# BleepDrum.net
KiCad netlist of a schematic drawn in EAGLE
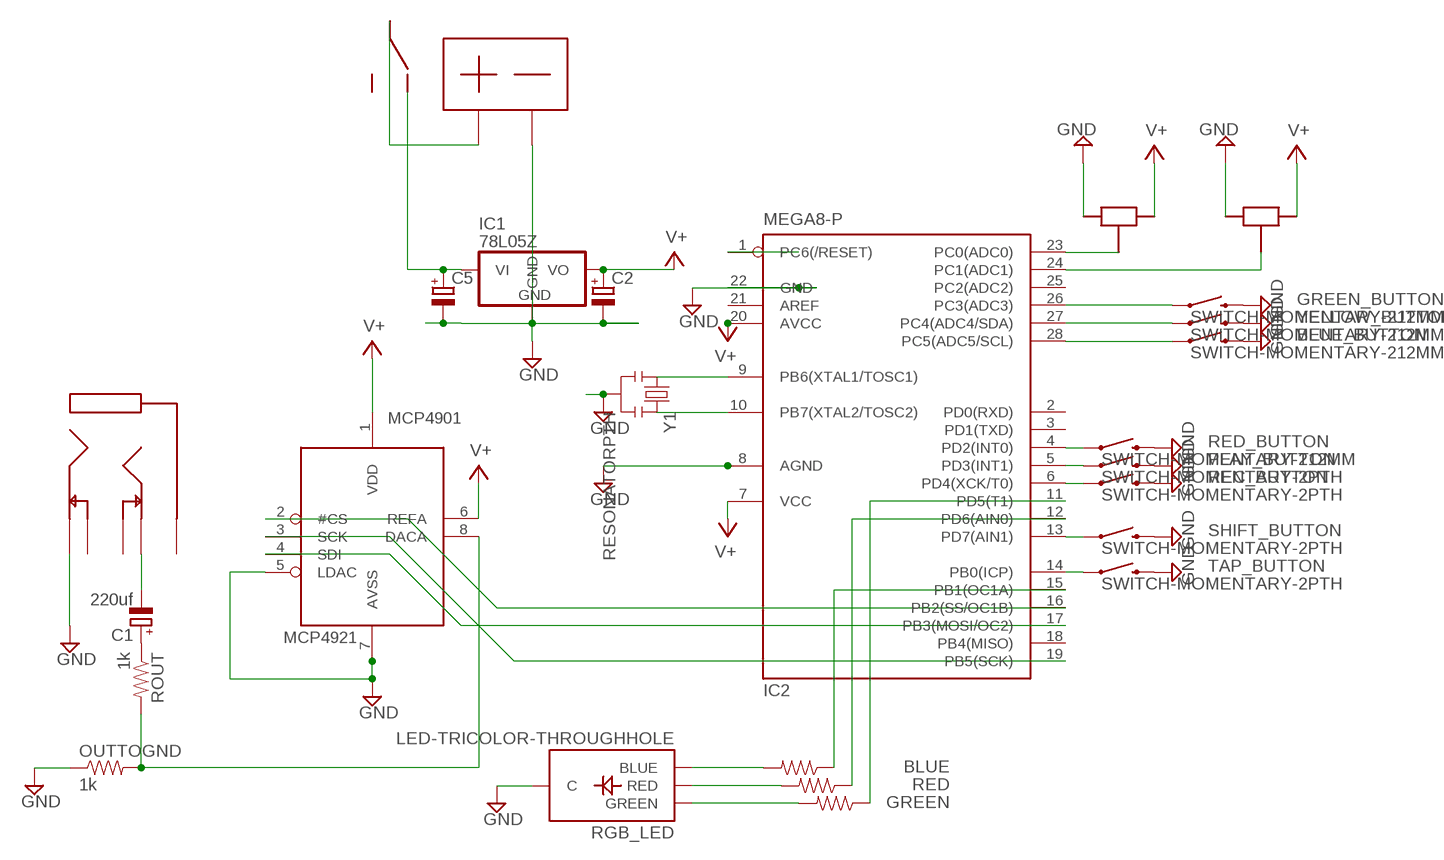
[diagram p0: schematic, sheet 1]

(export (version "E")
  (design (tool "Eeschema 10.0.6"))
  (components
    (comp (ref "BLUE")
      (value "RESISTORPTH-1/6W")
      (footprint "eagle-import:1_6W-RES")
      (libsource (lib "eagle-import") (part "RESISTORPTH-1/6W"))
    )
    (comp (ref "BLUE_BUTTON")
      (value "SWITCH-MOMENTARY-212MM")
      (footprint "eagle-import:TACTILE-PTH-12MM")
      (libsource (lib "eagle-import") (part "SWITCH-MOMENTARY-212MM"))
    )
    (comp (ref "C1")
      (value "220uf")
      (footprint "eagle-import:E2,5-6")
      (libsource (lib "eagle-import") (part "CPOL-EUE2.5-6"))
    )
    (comp (ref "C2")
      (value "CPOL-EUE2.5-6")
      (footprint "eagle-import:E2,5-6")
      (libsource (lib "eagle-import") (part "CPOL-EUE2.5-6"))
    )
    (comp (ref "C5")
      (value "CPOL-EUE2.5-6")
      (footprint "eagle-import:E2,5-6")
      (libsource (lib "eagle-import") (part "CPOL-EUE2.5-6"))
    )
    (comp (ref "GREEN")
      (value "RESISTORPTH-1/6W")
      (footprint "eagle-import:1_6W-RES")
      (libsource (lib "eagle-import") (part "RESISTORPTH-1/6W"))
    )
    (comp (ref "GREEN_BUTTON")
      (value "SWITCH-MOMENTARY-212MM")
      (footprint "eagle-import:TACTILE-PTH-12MM")
      (libsource (lib "eagle-import") (part "SWITCH-MOMENTARY-212MM"))
    )
    (comp (ref "IC1")
      (value "78L05Z")
      (footprint "eagle-import:TO92")
      (libsource (lib "eagle-import") (part "78ZL05"))
    )
    (comp (ref "IC2")
      (value "MEGA8-P")
      (footprint "eagle-import:DIL28-3")
      (libsource (lib "eagle-import") (part "MEGA8-P"))
    )
    (comp (ref "LEFT_POT")
      (value "POT")
      (footprint "eagle-import:POT")
      (libsource (lib "eagle-import") (part "POT"))
    )
    (comp (ref "MCP4901")
      (value "MCP4921")
      (footprint "eagle-import:DIL08")
      (libsource (lib "eagle-import") (part "MCP4921"))
    )
    (comp (ref "OUTTOGND")
      (value "1k")
      (footprint "eagle-import:1_6W-RES")
      (libsource (lib "eagle-import") (part "RESISTORPTH-1/6W"))
    )
    (comp (ref "PLAY_BUTTON")
      (value "SWITCH-MOMENTARY-2PTH")
      (footprint "eagle-import:TACTILE-PTH")
      (libsource (lib "eagle-import") (part "SWITCH-MOMENTARY-2PTH"))
    )
    (comp (ref "REC_BUTTON")
      (value "SWITCH-MOMENTARY-2PTH")
      (footprint "eagle-import:TACTILE-PTH")
      (libsource (lib "eagle-import") (part "SWITCH-MOMENTARY-2PTH"))
    )
    (comp (ref "RED")
      (value "RESISTORPTH-1/6W")
      (footprint "eagle-import:1_6W-RES")
      (libsource (lib "eagle-import") (part "RESISTORPTH-1/6W"))
    )
    (comp (ref "RED_BUTTON")
      (value "SWITCH-MOMENTARY-212MM")
      (footprint "eagle-import:TACTILE-PTH-12MM")
      (libsource (lib "eagle-import") (part "SWITCH-MOMENTARY-212MM"))
    )
    (comp (ref "RGB_LED")
      (value "LED-TRICOLOR-THROUGHHOLE")
      (footprint "eagle-import:LED-TRICOLOR-THROUGHHOLE")
      (libsource (lib "eagle-import") (part "LED-TRICOLOR-THROUGHHOLE"))
    )
    (comp (ref "RIGHT_POT")
      (value "POT")
      (footprint "eagle-import:POT")
      (libsource (lib "eagle-import") (part "POT"))
    )
    (comp (ref "ROUT")
      (value "1k")
      (footprint "eagle-import:1_6W-RES")
      (libsource (lib "eagle-import") (part "RESISTORPTH-1/6W"))
    )
    (comp (ref "SHIFT_BUTTON")
      (value "SWITCH-MOMENTARY-2PTH")
      (footprint "eagle-import:TACTILE-PTH")
      (libsource (lib "eagle-import") (part "SWITCH-MOMENTARY-2PTH"))
    )
    (comp (ref "SW1")
      (value "SLIDE_HORIZ_OS")
      (footprint "eagle-import:SLIDE_HORIZ_OS")
      (libsource (lib "eagle-import") (part "SLIDE_HORIZ_OS"))
    )
    (comp (ref "TAP_BUTTON")
      (value "SWITCH-MOMENTARY-2PTH")
      (footprint "eagle-import:TACTILE-PTH")
      (libsource (lib "eagle-import") (part "SWITCH-MOMENTARY-2PTH"))
    )
    (comp (ref "U$7")
      (value "9VSMALPINS")
      (footprint "eagle-import:9VSMALLPINS")
      (libsource (lib "eagle-import") (part "9VSMALPINS"))
    )
    (comp (ref "U$8")
      (value "1/8STEREO")
      (footprint "eagle-import:1_8STEREO")
      (libsource (lib "eagle-import") (part "1/8STEREO"))
    )
    (comp (ref "Y1")
      (value "RESONATORPTH")
      (footprint "eagle-import:RESONATOR-PTH")
      (libsource (lib "eagle-import") (part "RESONATORPTH"))
    )
    (comp (ref "YELLOW_BUTTON")
      (value "SWITCH-MOMENTARY-212MM")
      (footprint "eagle-import:TACTILE-PTH-12MM")
      (libsource (lib "eagle-import") (part "SWITCH-MOMENTARY-212MM"))
    )
  )
  (nets
    (net (code "1") (name "GND") (class "Default")
      (node (ref "BLUE_BUTTON") (pin "3") (pinfunction "2_3") (pintype "passive"))
      (node (ref "C2") (pin "-") (pinfunction "-_-") (pintype "passive"))
      (node (ref "C5") (pin "-") (pinfunction "-_-") (pintype "passive"))
      (node (ref "GREEN_BUTTON") (pin "3") (pinfunction "2_3") (pintype "passive"))
      (node (ref "IC1") (pin "2") (pinfunction "GND_2") (pintype "passive"))
      (node (ref "IC2") (pin "22") (pinfunction "GND_22") (pintype "power_in"))
      (node (ref "IC2") (pin "8") (pinfunction "AGND_8") (pintype "power_in"))
      (node (ref "LEFT_POT") (pin "P$3") (pinfunction "P$3_P$3") (pintype "bidirectional"))
      (node (ref "MCP4901") (pin "5") (pinfunction "LDAC_5") (pintype "input"))
      (node (ref "MCP4901") (pin "7") (pinfunction "AVSS_7") (pintype "power_in"))
      (node (ref "OUTTOGND") (pin "1") (pinfunction "1_1") (pintype "passive"))
      (node (ref "PLAY_BUTTON") (pin "3") (pinfunction "2_3") (pintype "passive"))
      (node (ref "REC_BUTTON") (pin "3") (pinfunction "2_3") (pintype "passive"))
      (node (ref "RED_BUTTON") (pin "3") (pinfunction "2_3") (pintype "passive"))
      (node (ref "RGB_LED") (pin "GND") (pinfunction "C_GND") (pintype "bidirectional"))
      (node (ref "RIGHT_POT") (pin "P$3") (pinfunction "P$3_P$3") (pintype "bidirectional"))
      (node (ref "SHIFT_BUTTON") (pin "3") (pinfunction "2_3") (pintype "passive"))
      (node (ref "TAP_BUTTON") (pin "3") (pinfunction "2_3") (pintype "passive"))
      (node (ref "U$7") (pin "P$2") (pinfunction "P$2_P$2") (pintype "bidirectional"))
      (node (ref "U$8") (pin "P$2") (pinfunction "P$2_P$2") (pintype "bidirectional"))
      (node (ref "Y1") (pin "2") (pinfunction "2_2") (pintype "passive"))
      (node (ref "YELLOW_BUTTON") (pin "3") (pinfunction "2_3") (pintype "passive"))
    )
    (net (code "2") (name "Net-(C1-Pad+)") (class "Default")
      (node (ref "C1") (pin "+") (pinfunction "+_+") (pintype "passive"))
      (node (ref "ROUT") (pin "1") (pinfunction "1_1") (pintype "passive"))
    )
    (net (code "3") (name "Net-(C1-Pad-)") (class "Default")
      (node (ref "C1") (pin "-") (pinfunction "-_-") (pintype "passive"))
      (node (ref "U$8") (pin "P$5") (pinfunction "P$5_P$5") (pintype "bidirectional"))
    )
    (net (code "4") (name "Net-(IC1-VI)") (class "Default")
      (node (ref "C5") (pin "+") (pinfunction "+_+") (pintype "passive"))
      (node (ref "IC1") (pin "3") (pinfunction "VI_3") (pintype "input"))
      (node (ref "SW1") (pin "P$2") (pinfunction "P$2_P$2") (pintype "bidirectional"))
    )
    (net (code "5") (name "Net-(IC2-PB0(ICP))") (class "Default")
      (node (ref "IC2") (pin "14") (pinfunction "PB0(ICP)_14") (pintype "bidirectional"))
      (node (ref "TAP_BUTTON") (pin "1") (pinfunction "1_1") (pintype "passive"))
    )
    (net (code "6") (name "Net-(IC2-PB1(OC1A))") (class "Default")
      (node (ref "BLUE") (pin "1") (pinfunction "1_1") (pintype "passive"))
      (node (ref "IC2") (pin "15") (pinfunction "PB1(OC1A)_15") (pintype "bidirectional"))
    )
    (net (code "7") (name "Net-(IC2-PB2(SS{slash}OC1B))") (class "Default")
      (node (ref "IC2") (pin "16") (pinfunction "PB2(SS/OC1B)_16") (pintype "bidirectional"))
      (node (ref "MCP4901") (pin "2") (pinfunction "#CS_2") (pintype "input"))
    )
    (net (code "8") (name "Net-(IC2-PB3(MOSI{slash}OC2))") (class "Default")
      (node (ref "IC2") (pin "17") (pinfunction "PB3(MOSI/OC2)_17") (pintype "bidirectional"))
      (node (ref "MCP4901") (pin "4") (pinfunction "SDI_4") (pintype "input"))
    )
    (net (code "9") (name "Net-(IC2-PB5(SCK))") (class "Default")
      (node (ref "IC2") (pin "19") (pinfunction "PB5(SCK)_19") (pintype "bidirectional"))
      (node (ref "MCP4901") (pin "3") (pinfunction "SCK_3") (pintype "input"))
    )
    (net (code "10") (name "Net-(IC2-PB6(XTAL1{slash}TOSC1))") (class "Default")
      (node (ref "IC2") (pin "9") (pinfunction "PB6(XTAL1/TOSC1)_9") (pintype "bidirectional"))
      (node (ref "Y1") (pin "1") (pinfunction "1_1") (pintype "passive"))
    )
    (net (code "11") (name "Net-(IC2-PB7(XTAL2{slash}TOSC2))") (class "Default")
      (node (ref "IC2") (pin "10") (pinfunction "PB7(XTAL2/TOSC2)_10") (pintype "bidirectional"))
      (node (ref "Y1") (pin "3") (pinfunction "3_3") (pintype "passive"))
    )
    (net (code "12") (name "Net-(IC2-PC0(ADC0))") (class "Default")
      (node (ref "IC2") (pin "23") (pinfunction "PC0(ADC0)_23") (pintype "bidirectional"))
      (node (ref "RIGHT_POT") (pin "P$2") (pinfunction "P$2_P$2") (pintype "bidirectional"))
    )
    (net (code "13") (name "Net-(IC2-PC1(ADC1))") (class "Default")
      (node (ref "IC2") (pin "24") (pinfunction "PC1(ADC1)_24") (pintype "bidirectional"))
      (node (ref "LEFT_POT") (pin "P$2") (pinfunction "P$2_P$2") (pintype "bidirectional"))
    )
    (net (code "14") (name "Net-(IC2-PC3(ADC3))") (class "Default")
      (node (ref "GREEN_BUTTON") (pin "1") (pinfunction "1_1") (pintype "passive"))
      (node (ref "IC2") (pin "26") (pinfunction "PC3(ADC3)_26") (pintype "bidirectional"))
    )
    (net (code "15") (name "Net-(IC2-PC4(ADC4{slash}SDA))") (class "Default")
      (node (ref "IC2") (pin "27") (pinfunction "PC4(ADC4/SDA)_27") (pintype "bidirectional"))
      (node (ref "YELLOW_BUTTON") (pin "1") (pinfunction "1_1") (pintype "passive"))
    )
    (net (code "16") (name "Net-(IC2-PC5(ADC5{slash}SCL))") (class "Default")
      (node (ref "BLUE_BUTTON") (pin "1") (pinfunction "1_1") (pintype "passive"))
      (node (ref "IC2") (pin "28") (pinfunction "PC5(ADC5/SCL)_28") (pintype "bidirectional"))
    )
    (net (code "17") (name "Net-(IC2-PD2(INT0))") (class "Default")
      (node (ref "IC2") (pin "4") (pinfunction "PD2(INT0)_4") (pintype "bidirectional"))
      (node (ref "RED_BUTTON") (pin "1") (pinfunction "1_1") (pintype "passive"))
    )
    (net (code "18") (name "Net-(IC2-PD3(INT1))") (class "Default")
      (node (ref "IC2") (pin "5") (pinfunction "PD3(INT1)_5") (pintype "bidirectional"))
      (node (ref "PLAY_BUTTON") (pin "1") (pinfunction "1_1") (pintype "passive"))
    )
    (net (code "19") (name "Net-(IC2-PD4(XCK{slash}T0))") (class "Default")
      (node (ref "IC2") (pin "6") (pinfunction "PD4(XCK/T0)_6") (pintype "bidirectional"))
      (node (ref "REC_BUTTON") (pin "1") (pinfunction "1_1") (pintype "passive"))
    )
    (net (code "20") (name "Net-(IC2-PD5(T1))") (class "Default")
      (node (ref "GREEN") (pin "1") (pinfunction "1_1") (pintype "passive"))
      (node (ref "IC2") (pin "11") (pinfunction "PD5(T1)_11") (pintype "bidirectional"))
    )
    (net (code "21") (name "Net-(IC2-PD6(AIN0))") (class "Default")
      (node (ref "IC2") (pin "12") (pinfunction "PD6(AIN0)_12") (pintype "bidirectional"))
      (node (ref "RED") (pin "1") (pinfunction "1_1") (pintype "passive"))
    )
    (net (code "22") (name "Net-(IC2-PD7(AIN1))") (class "Default")
      (node (ref "IC2") (pin "13") (pinfunction "PD7(AIN1)_13") (pintype "bidirectional"))
      (node (ref "SHIFT_BUTTON") (pin "1") (pinfunction "1_1") (pintype "passive"))
    )
    (net (code "23") (name "Net-(MCP4901-DACA)") (class "Default")
      (node (ref "MCP4901") (pin "8") (pinfunction "DACA_8") (pintype "output"))
      (node (ref "OUTTOGND") (pin "2") (pinfunction "2_2") (pintype "passive"))
      (node (ref "ROUT") (pin "2") (pinfunction "2_2") (pintype "passive"))
    )
    (net (code "24") (name "Net-(RGB_LED-BLUE)") (class "Default")
      (node (ref "BLUE") (pin "2") (pinfunction "2_2") (pintype "passive"))
      (node (ref "RGB_LED") (pin "GRN") (pinfunction "BLUE_GRN") (pintype "bidirectional"))
    )
    (net (code "25") (name "Net-(RGB_LED-GREEN)") (class "Default")
      (node (ref "GREEN") (pin "2") (pinfunction "2_2") (pintype "passive"))
      (node (ref "RGB_LED") (pin "RED") (pinfunction "GREEN_RED") (pintype "bidirectional"))
    )
    (net (code "26") (name "Net-(RGB_LED-RED)") (class "Default")
      (node (ref "RED") (pin "2") (pinfunction "2_2") (pintype "passive"))
      (node (ref "RGB_LED") (pin "BLU") (pinfunction "RED_BLU") (pintype "bidirectional"))
    )
    (net (code "27") (name "Net-(SW1-PadP$1)") (class "Default")
      (node (ref "SW1") (pin "P$1") (pinfunction "P$1_P$1") (pintype "bidirectional"))
      (node (ref "U$7") (pin "P$1") (pinfunction "P$1_P$1") (pintype "bidirectional"))
    )
    (net (code "28") (name "V+") (class "Default")
      (node (ref "C2") (pin "+") (pinfunction "+_+") (pintype "passive"))
      (node (ref "IC1") (pin "1") (pinfunction "VO_1") (pintype "passive"))
      (node (ref "IC2") (pin "20") (pinfunction "AVCC_20") (pintype "power_in"))
      (node (ref "IC2") (pin "7") (pinfunction "VCC_7") (pintype "power_in"))
      (node (ref "LEFT_POT") (pin "P$1") (pinfunction "P$1_P$1") (pintype "bidirectional"))
      (node (ref "MCP4901") (pin "1") (pinfunction "VDD_1") (pintype "power_in"))
      (node (ref "MCP4901") (pin "6") (pinfunction "REFA_6") (pintype "input"))
      (node (ref "RIGHT_POT") (pin "P$1") (pinfunction "P$1_P$1") (pintype "bidirectional"))
    )
    (net (code "29") (name "unconnected-(IC2-AREF-Pad21)") (class "Default")
      (node (ref "IC2") (pin "21") (pinfunction "AREF_21") (pintype "passive"))
    )
    (net (code "30") (name "unconnected-(IC2-PB4(MISO)-Pad18)") (class "Default")
      (node (ref "IC2") (pin "18") (pinfunction "PB4(MISO)_18") (pintype "bidirectional"))
    )
    (net (code "31") (name "unconnected-(IC2-PC2(ADC2)-Pad25)") (class "Default")
      (node (ref "IC2") (pin "25") (pinfunction "PC2(ADC2)_25") (pintype "bidirectional"))
    )
    (net (code "32") (name "unconnected-(IC2-PC6({slash}RESET)-Pad1)") (class "Default")
      (node (ref "IC2") (pin "1") (pinfunction "PC6(/RESET)_1") (pintype "bidirectional"))
    )
    (net (code "33") (name "unconnected-(IC2-PD0(RXD)-Pad2)") (class "Default")
      (node (ref "IC2") (pin "2") (pinfunction "PD0(RXD)_2") (pintype "bidirectional"))
    )
    (net (code "34") (name "unconnected-(IC2-PD1(TXD)-Pad3)") (class "Default")
      (node (ref "IC2") (pin "3") (pinfunction "PD1(TXD)_3") (pintype "bidirectional"))
    )
    (net (code "35") (name "unconnected-(SW1-PadP$3)") (class "Default")
      (node (ref "SW1") (pin "P$3") (pinfunction "P$3_P$3") (pintype "bidirectional"))
    )
    (net (code "36") (name "unconnected-(U$8-PadP$1)") (class "Default")
      (node (ref "U$8") (pin "P$1") (pinfunction "P$1_P$1") (pintype "bidirectional"))
    )
    (net (code "37") (name "unconnected-(U$8-PadP$3)") (class "Default")
      (node (ref "U$8") (pin "P$3") (pinfunction "P$3_P$3") (pintype "bidirectional"))
    )
    (net (code "38") (name "unconnected-(U$8-PadP$4)") (class "Default")
      (node (ref "U$8") (pin "P$4") (pinfunction "P$4_P$4") (pintype "bidirectional"))
    )
  )
)
